# MegaShieldDB.net
KiCad netlist of a schematic drawn in EAGLE
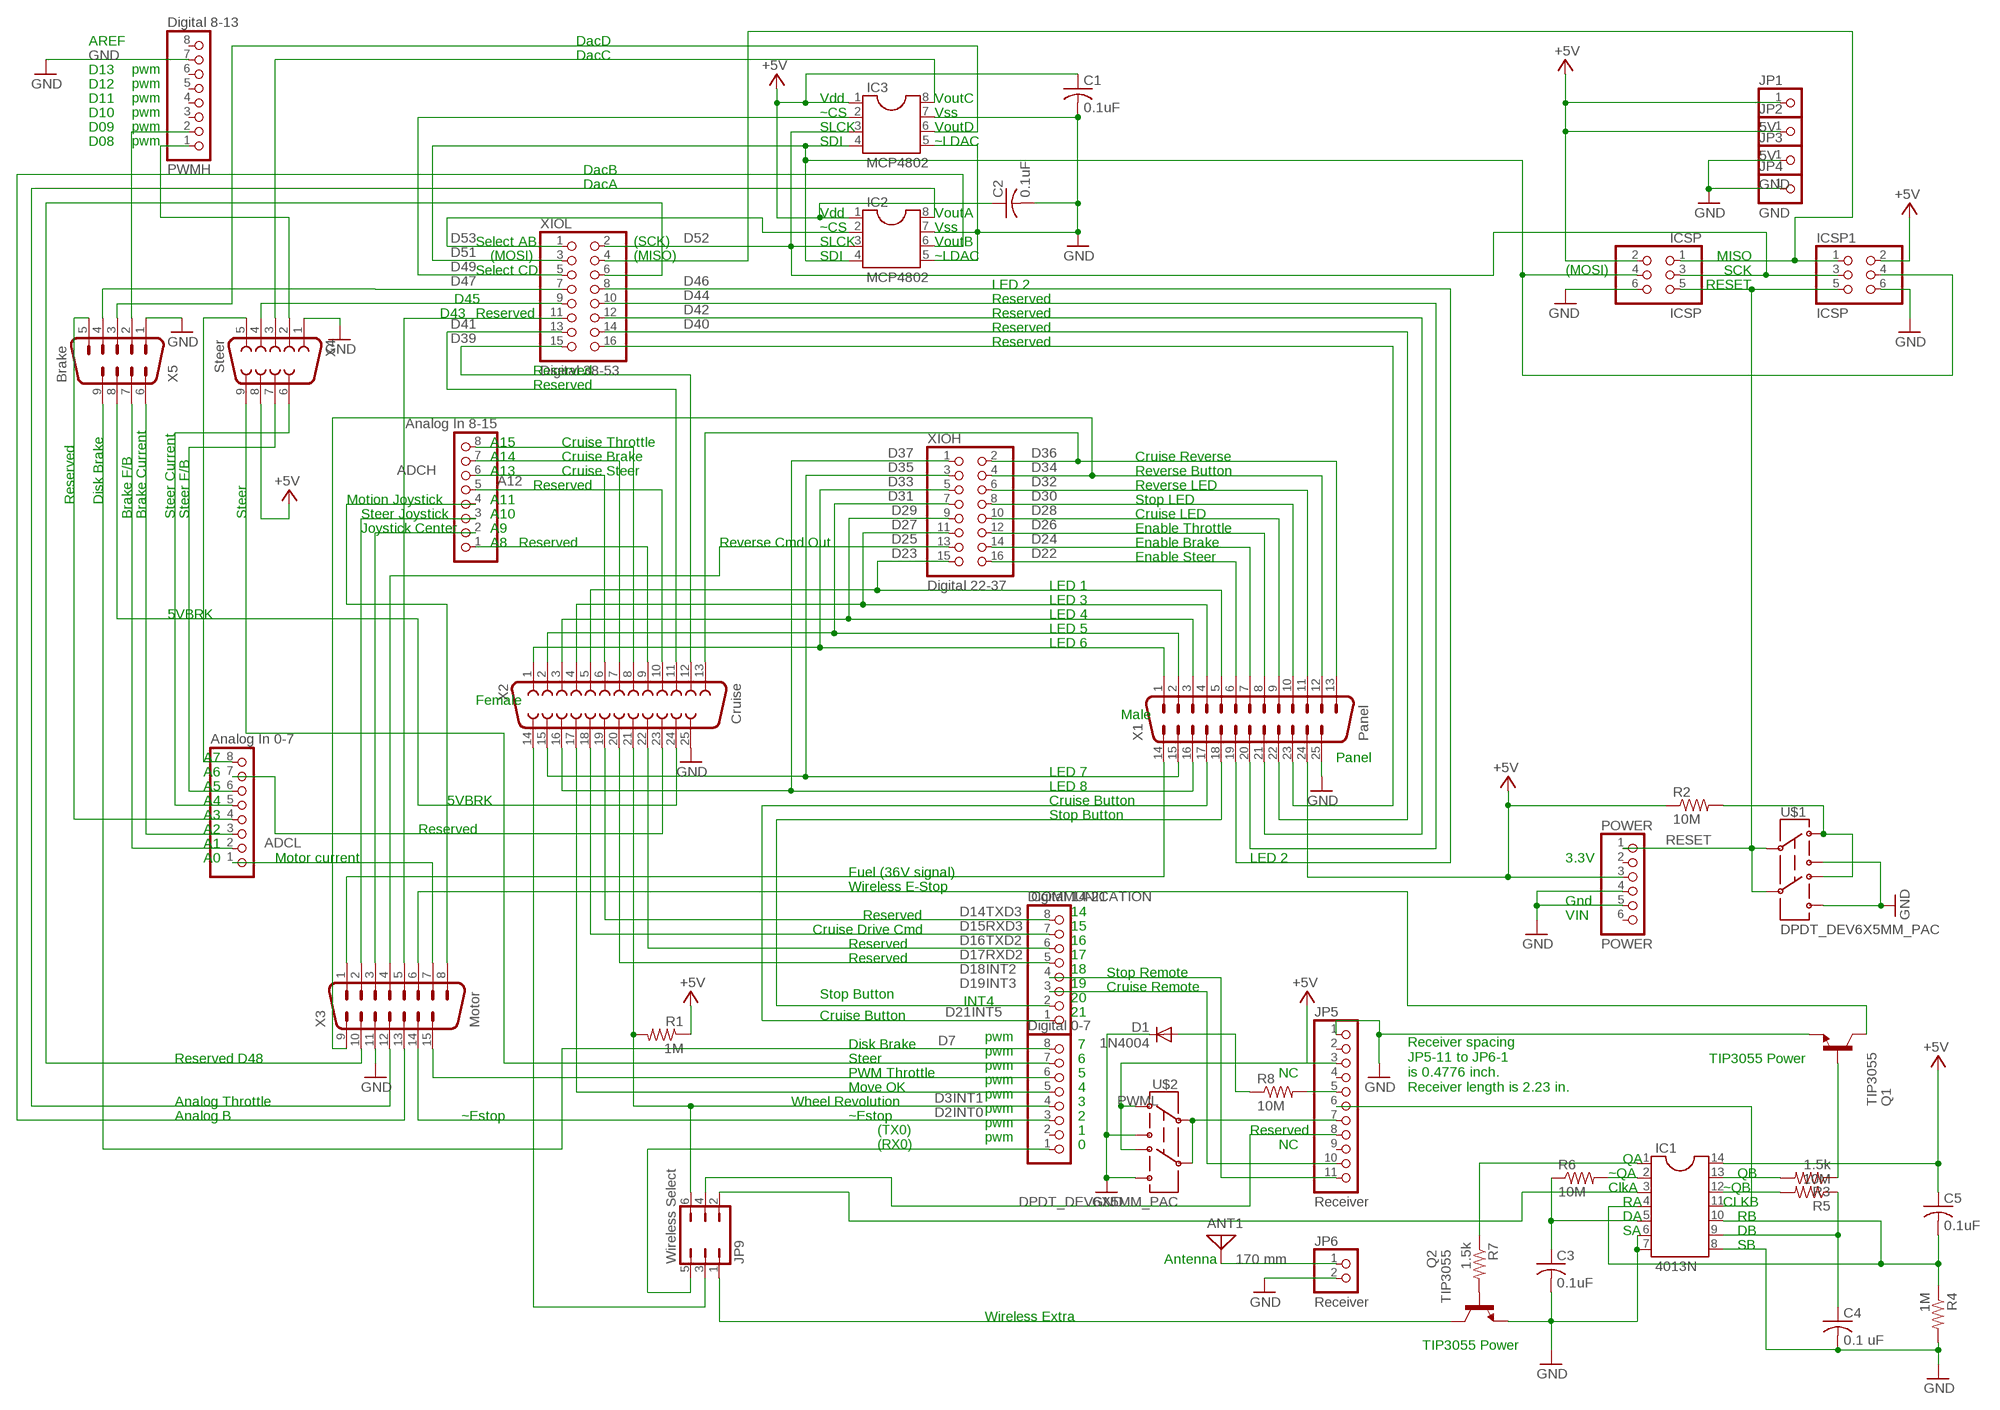
[diagram p0: schematic, sheet 1]

(export (version "E")
  (design (tool "Eeschema 10.0.6"))
  (components
    (comp (ref "ADCH")
      (value "Analog In 8-15")
      (footprint "eagle-import:1X08")
      (libsource (lib "eagle-import") (part "PINHD-1X8"))
    )
    (comp (ref "ADCL")
      (value "Analog In 0-7")
      (footprint "eagle-import:1X08")
      (libsource (lib "eagle-import") (part "PINHD-1X8"))
    )
    (comp (ref "ANT1")
      (value "170 mm")
      (footprint "eagle-import:PAD-01")
      (libsource (lib "eagle-import") (part "ANTENNA"))
    )
    (comp (ref "C1")
      (value "0.1uF")
      (footprint "eagle-import:C025-025X050")
      (libsource (lib "eagle-import") (part "C-US025-025X050"))
    )
    (comp (ref "C2")
      (value "0.1uF")
      (footprint "eagle-import:C025-025X050")
      (libsource (lib "eagle-import") (part "C-US025-025X050"))
    )
    (comp (ref "C3")
      (value "0.1uF")
      (footprint "eagle-import:C025-025X050")
      (libsource (lib "eagle-import") (part "C-US025-025X050"))
    )
    (comp (ref "C4")
      (value "0.1 uF")
      (footprint "eagle-import:C025-025X050")
      (libsource (lib "eagle-import") (part "C-US025-025X050"))
    )
    (comp (ref "C5")
      (value "0.1uF")
      (footprint "eagle-import:C025-025X050")
      (libsource (lib "eagle-import") (part "C-US025-025X050"))
    )
    (comp (ref "COMMUNICATION")
      (value "Digital 14-21")
      (footprint "eagle-import:1X08")
      (libsource (lib "eagle-import") (part "PINHD-1X8"))
    )
    (comp (ref "D1")
      (value "1N4004")
      (footprint "eagle-import:DO41-10")
      (libsource (lib "eagle-import") (part "1N4004"))
    )
    (comp (ref "IC1")
      (value "4013N")
      (footprint "eagle-import:DIL14")
      (libsource (lib "eagle-import") (part "DIL14"))
    )
    (comp (ref "IC2")
      (value "MCP4802")
      (footprint "eagle-import:DIL08")
      (libsource (lib "eagle-import") (part "DIL8"))
    )
    (comp (ref "IC3")
      (value "MCP4802")
      (footprint "eagle-import:DIL08")
      (libsource (lib "eagle-import") (part "DIL8"))
    )
    (comp (ref "ICSP")
      (value "ICSP")
      (footprint "eagle-import:2X03")
      (libsource (lib "eagle-import") (part "PINHD-2X3"))
    )
    (comp (ref "ICSP1")
      (value "ICSP")
      (footprint "eagle-import:2X03")
      (libsource (lib "eagle-import") (part "PINHD-2X3"))
    )
    (comp (ref "JP1")
      (value "5V")
      (footprint "eagle-import:1X01")
      (libsource (lib "eagle-import") (part "PINHD-1X1"))
    )
    (comp (ref "JP2")
      (value "5V")
      (footprint "eagle-import:1X01")
      (libsource (lib "eagle-import") (part "PINHD-1X1"))
    )
    (comp (ref "JP3")
      (value "GND")
      (footprint "eagle-import:1X01")
      (libsource (lib "eagle-import") (part "PINHD-1X1"))
    )
    (comp (ref "JP4")
      (value "GND")
      (footprint "eagle-import:1X01")
      (libsource (lib "eagle-import") (part "PINHD-1X1"))
    )
    (comp (ref "JP5")
      (value "Receiver")
      (footprint "eagle-import:1X11")
      (libsource (lib "eagle-import") (part "PINHD-1X11"))
    )
    (comp (ref "JP6")
      (value "Receiver")
      (footprint "eagle-import:1X02")
      (libsource (lib "eagle-import") (part "PINHD-1X2"))
    )
    (comp (ref "JP9")
      (value "Wireless Select")
      (footprint "eagle-import:JP3Q")
      (libsource (lib "eagle-import") (part "JP3Q"))
    )
    (comp (ref "POWER")
      (value "POWER")
      (footprint "eagle-import:1X06")
      (libsource (lib "eagle-import") (part "PINHD-1X6"))
    )
    (comp (ref "PWMH")
      (value "Digital 8-13")
      (footprint "eagle-import:1X08")
      (libsource (lib "eagle-import") (part "PINHD-1X8"))
    )
    (comp (ref "PWML")
      (value "Digital 0-7")
      (footprint "eagle-import:1X08")
      (libsource (lib "eagle-import") (part "PINHD-1X8"))
    )
    (comp (ref "Q1")
      (value "TIP3055")
      (footprint "eagle-import:TO220")
      (libsource (lib "eagle-import") (part "BD535"))
    )
    (comp (ref "Q2")
      (value "TIP3055")
      (footprint "eagle-import:TO220")
      (libsource (lib "eagle-import") (part "BD535"))
    )
    (comp (ref "R1")
      (value "1M")
      (footprint "eagle-import:0204_5")
      (libsource (lib "eagle-import") (part "R-US_0204/5"))
    )
    (comp (ref "R2")
      (value "10M")
      (footprint "eagle-import:0204_5")
      (libsource (lib "eagle-import") (part "R-US_0204/5"))
    )
    (comp (ref "R3")
      (value "1.5k")
      (footprint "eagle-import:0204_5")
      (libsource (lib "eagle-import") (part "R-US_0204/5"))
    )
    (comp (ref "R4")
      (value "1M")
      (footprint "eagle-import:0204_5")
      (libsource (lib "eagle-import") (part "R-US_0204/5"))
    )
    (comp (ref "R5")
      (value "10M")
      (footprint "eagle-import:0204_5")
      (libsource (lib "eagle-import") (part "R-US_0204/5"))
    )
    (comp (ref "R6")
      (value "10M")
      (footprint "eagle-import:0204_5")
      (libsource (lib "eagle-import") (part "R-US_0204/5"))
    )
    (comp (ref "R7")
      (value "1.5k")
      (footprint "eagle-import:0204_5")
      (libsource (lib "eagle-import") (part "R-US_0204/5"))
    )
    (comp (ref "R8")
      (value "10M")
      (footprint "eagle-import:0204_5")
      (libsource (lib "eagle-import") (part "R-US_0204/5"))
    )
    (comp (ref "U$1")
      (value "DPDT_DEV6X5MM_PAC")
      (footprint "eagle-import:NEWSWITCH2_PAC")
      (libsource (lib "eagle-import") (part "DPDT_DEV6X5MM_PAC"))
    )
    (comp (ref "U$2")
      (value "DPDT_DEV6X5MM_PAC")
      (footprint "eagle-import:NEWSWITCH2_PAC")
      (libsource (lib "eagle-import") (part "DPDT_DEV6X5MM_PAC"))
    )
    (comp (ref "X1")
      (value "Panel")
      (footprint "eagle-import:M25-HD-20")
      (libsource (lib "eagle-import") (part "M25-HD-20"))
    )
    (comp (ref "X2")
      (value "Cruise")
      (footprint "eagle-import:F25H")
      (libsource (lib "eagle-import") (part "F25H"))
    )
    (comp (ref "X3")
      (value "Motor")
      (footprint "eagle-import:182-015-MALE")
      (libsource (lib "eagle-import") (part "M15-182"))
    )
    (comp (ref "X4")
      (value "Steer")
      (footprint "eagle-import:F09H")
      (libsource (lib "eagle-import") (part "F09H"))
    )
    (comp (ref "X5")
      (value "Brake")
      (footprint "eagle-import:182-009-MALE")
      (libsource (lib "eagle-import") (part "M09-182"))
    )
    (comp (ref "XIOH")
      (value "Digital 22-37")
      (footprint "eagle-import:2X08")
      (libsource (lib "eagle-import") (part "PINHD-2X8"))
    )
    (comp (ref "XIOL")
      (value "Digital 38-53")
      (footprint "eagle-import:2X08")
      (libsource (lib "eagle-import") (part "PINHD-2X8"))
    )
  )
  (nets
    (net (code "1") (name "+5V") (class "Default")
      (node (ref "C1") (pin "1") (pinfunction "1_1") (pintype "passive"))
      (node (ref "C2") (pin "1") (pinfunction "1_1") (pintype "passive"))
      (node (ref "C5") (pin "1") (pinfunction "1_1") (pintype "passive"))
      (node (ref "IC1") (pin "14") (pinfunction "14_14") (pintype "passive"))
      (node (ref "IC2") (pin "1") (pinfunction "1_1") (pintype "passive"))
      (node (ref "IC3") (pin "1") (pinfunction "1_1") (pintype "passive"))
      (node (ref "ICSP") (pin "2") (pinfunction "2_2") (pintype "passive"))
      (node (ref "ICSP1") (pin "2") (pinfunction "2_2") (pintype "passive"))
      (node (ref "JP1") (pin "1") (pinfunction "1_1") (pintype "passive"))
      (node (ref "JP2") (pin "1") (pinfunction "1_1") (pintype "passive"))
      (node (ref "JP5") (pin "3") (pinfunction "3_3") (pintype "passive"))
      (node (ref "POWER") (pin "3") (pinfunction "3_3") (pintype "passive"))
      (node (ref "R1") (pin "1") (pinfunction "1_1") (pintype "passive"))
      (node (ref "R2") (pin "1") (pinfunction "1_1") (pintype "passive"))
      (node (ref "U$2") (pin "PIN1") (pinfunction "1_PIN1") (pintype "bidirectional"))
      (node (ref "U$2") (pin "PIN4") (pinfunction "4_PIN4") (pintype "bidirectional"))
      (node (ref "X1") (pin "24") (pinfunction "24_24") (pintype "passive"))
      (node (ref "X4") (pin "8") (pinfunction "8_8") (pintype "passive"))
    )
    (net (code "2") (name "/A12") (class "Default")
      (node (ref "ADCH") (pin "5") (pinfunction "5_5") (pintype "passive"))
      (node (ref "X2") (pin "10") (pinfunction "10_10") (pintype "passive"))
    )
    (net (code "3") (name "/D2INT0") (class "Default")
      (node (ref "PWML") (pin "3") (pinfunction "3_3") (pintype "passive"))
      (node (ref "X3") (pin "14") (pinfunction "14_14") (pintype "passive"))
    )
    (net (code "4") (name "/D3INT1") (class "Default")
      (node (ref "JP9") (pin "6") (pinfunction "6_6") (pintype "passive"))
      (node (ref "PWML") (pin "4") (pinfunction "4_4") (pintype "passive"))
      (node (ref "R1") (pin "2") (pinfunction "2_2") (pintype "passive"))
      (node (ref "X2") (pin "21") (pinfunction "21_21") (pintype "passive"))
    )
    (net (code "5") (name "/D7") (class "Default")
      (node (ref "PWML") (pin "8") (pinfunction "8_8") (pintype "passive"))
      (node (ref "X5") (pin "9") (pinfunction "9_9") (pintype "passive"))
    )
    (net (code "6") (name "/D14TXD3") (class "Default")
      (node (ref "COMMUNICATION") (pin "8") (pinfunction "8_8") (pintype "passive"))
      (node (ref "X2") (pin "19") (pinfunction "19_19") (pintype "passive"))
    )
    (net (code "7") (name "/D15RXD3") (class "Default")
      (node (ref "COMMUNICATION") (pin "7") (pinfunction "7_7") (pintype "passive"))
      (node (ref "X2") (pin "18") (pinfunction "18_18") (pintype "passive"))
    )
    (net (code "8") (name "/D16TXD2") (class "Default")
      (node (ref "COMMUNICATION") (pin "6") (pinfunction "6_6") (pintype "passive"))
      (node (ref "X2") (pin "22") (pinfunction "22_22") (pintype "passive"))
    )
    (net (code "9") (name "/D17RXD2") (class "Default")
      (node (ref "COMMUNICATION") (pin "5") (pinfunction "5_5") (pintype "passive"))
      (node (ref "X2") (pin "20") (pinfunction "20_20") (pintype "passive"))
    )
    (net (code "10") (name "/D18INT2") (class "Default")
      (node (ref "COMMUNICATION") (pin "4") (pinfunction "4_4") (pintype "passive"))
      (node (ref "JP5") (pin "11") (pinfunction "11_11") (pintype "passive"))
    )
    (net (code "11") (name "/D19INT3") (class "Default")
      (node (ref "COMMUNICATION") (pin "3") (pinfunction "3_3") (pintype "passive"))
      (node (ref "JP5") (pin "10") (pinfunction "10_10") (pintype "passive"))
    )
    (net (code "12") (name "/D21INT5") (class "Default")
      (node (ref "COMMUNICATION") (pin "1") (pinfunction "1_1") (pintype "passive"))
      (node (ref "X1") (pin "17") (pinfunction "17_17") (pintype "passive"))
    )
    (net (code "13") (name "/D22") (class "Default")
      (node (ref "X1") (pin "6") (pinfunction "6_6") (pintype "passive"))
      (node (ref "XIOH") (pin "16") (pinfunction "16_16") (pintype "passive"))
    )
    (net (code "14") (name "/D23") (class "Default")
      (node (ref "X1") (pin "5") (pinfunction "5_5") (pintype "passive"))
      (node (ref "X2") (pin "5") (pinfunction "5_5") (pintype "passive"))
      (node (ref "XIOH") (pin "15") (pinfunction "15_15") (pintype "passive"))
    )
    (net (code "15") (name "/D24") (class "Default")
      (node (ref "X1") (pin "7") (pinfunction "7_7") (pintype "passive"))
      (node (ref "XIOH") (pin "14") (pinfunction "14_14") (pintype "passive"))
    )
    (net (code "16") (name "/D25") (class "Default")
      (node (ref "X3") (pin "4") (pinfunction "4_4") (pintype "passive"))
      (node (ref "XIOH") (pin "13") (pinfunction "13_13") (pintype "passive"))
    )
    (net (code "17") (name "/D26") (class "Default")
      (node (ref "X1") (pin "8") (pinfunction "8_8") (pintype "passive"))
      (node (ref "XIOH") (pin "12") (pinfunction "12_12") (pintype "passive"))
    )
    (net (code "18") (name "/D27") (class "Default")
      (node (ref "X1") (pin "4") (pinfunction "4_4") (pintype "passive"))
      (node (ref "X2") (pin "4") (pinfunction "4_4") (pintype "passive"))
      (node (ref "XIOH") (pin "11") (pinfunction "11_11") (pintype "passive"))
    )
    (net (code "19") (name "/D28") (class "Default")
      (node (ref "X1") (pin "9") (pinfunction "9_9") (pintype "passive"))
      (node (ref "XIOH") (pin "10") (pinfunction "10_10") (pintype "passive"))
    )
    (net (code "20") (name "/D29") (class "Default")
      (node (ref "X1") (pin "3") (pinfunction "3_3") (pintype "passive"))
      (node (ref "X2") (pin "3") (pinfunction "3_3") (pintype "passive"))
      (node (ref "XIOH") (pin "9") (pinfunction "9_9") (pintype "passive"))
    )
    (net (code "21") (name "/D30") (class "Default")
      (node (ref "X1") (pin "10") (pinfunction "10_10") (pintype "passive"))
      (node (ref "XIOH") (pin "8") (pinfunction "8_8") (pintype "passive"))
    )
    (net (code "22") (name "/D31") (class "Default")
      (node (ref "X1") (pin "2") (pinfunction "2_2") (pintype "passive"))
      (node (ref "X2") (pin "2") (pinfunction "2_2") (pintype "passive"))
      (node (ref "XIOH") (pin "7") (pinfunction "7_7") (pintype "passive"))
    )
    (net (code "23") (name "/D32") (class "Default")
      (node (ref "X1") (pin "11") (pinfunction "11_11") (pintype "passive"))
      (node (ref "XIOH") (pin "6") (pinfunction "6_6") (pintype "passive"))
    )
    (net (code "24") (name "/D33") (class "Default")
      (node (ref "X1") (pin "1") (pinfunction "1_1") (pintype "passive"))
      (node (ref "X2") (pin "1") (pinfunction "1_1") (pintype "passive"))
      (node (ref "XIOH") (pin "5") (pinfunction "5_5") (pintype "passive"))
    )
    (net (code "25") (name "/D34") (class "Default")
      (node (ref "X1") (pin "12") (pinfunction "12_12") (pintype "passive"))
      (node (ref "X3") (pin "9") (pinfunction "9_9") (pintype "passive"))
      (node (ref "XIOH") (pin "4") (pinfunction "4_4") (pintype "passive"))
    )
    (net (code "26") (name "/D35") (class "Default")
      (node (ref "X1") (pin "15") (pinfunction "15_15") (pintype "passive"))
      (node (ref "X2") (pin "15") (pinfunction "15_15") (pintype "passive"))
      (node (ref "XIOH") (pin "3") (pinfunction "3_3") (pintype "passive"))
    )
    (net (code "27") (name "/D36") (class "Default")
      (node (ref "X1") (pin "13") (pinfunction "13_13") (pintype "passive"))
      (node (ref "X2") (pin "13") (pinfunction "13_13") (pintype "passive"))
      (node (ref "XIOH") (pin "2") (pinfunction "2_2") (pintype "passive"))
    )
    (net (code "28") (name "/D37") (class "Default")
      (node (ref "X1") (pin "16") (pinfunction "16_16") (pintype "passive"))
      (node (ref "X2") (pin "16") (pinfunction "16_16") (pintype "passive"))
      (node (ref "XIOH") (pin "1") (pinfunction "1_1") (pintype "passive"))
    )
    (net (code "29") (name "/D39") (class "Default")
      (node (ref "X2") (pin "12") (pinfunction "12_12") (pintype "passive"))
      (node (ref "XIOL") (pin "15") (pinfunction "15_15") (pintype "passive"))
    )
    (net (code "30") (name "/D40") (class "Default")
      (node (ref "X1") (pin "22") (pinfunction "22_22") (pintype "passive"))
      (node (ref "XIOL") (pin "14") (pinfunction "14_14") (pintype "passive"))
    )
    (net (code "31") (name "/D41") (class "Default")
      (node (ref "X2") (pin "11") (pinfunction "11_11") (pintype "passive"))
      (node (ref "XIOL") (pin "13") (pinfunction "13_13") (pintype "passive"))
    )
    (net (code "32") (name "/D42") (class "Default")
      (node (ref "X1") (pin "21") (pinfunction "21_21") (pintype "passive"))
      (node (ref "XIOL") (pin "12") (pinfunction "12_12") (pintype "passive"))
    )
    (net (code "33") (name "/D44") (class "Default")
      (node (ref "X1") (pin "20") (pinfunction "20_20") (pintype "passive"))
      (node (ref "XIOL") (pin "10") (pinfunction "10_10") (pintype "passive"))
    )
    (net (code "34") (name "/D46") (class "Default")
      (node (ref "X1") (pin "19") (pinfunction "19_19") (pintype "passive"))
      (node (ref "XIOL") (pin "8") (pinfunction "8_8") (pintype "passive"))
    )
    (net (code "35") (name "/D47") (class "Default")
      (node (ref "X5") (pin "4") (pinfunction "4_4") (pintype "passive"))
      (node (ref "XIOL") (pin "7") (pinfunction "7_7") (pintype "passive"))
    )
    (net (code "36") (name "/D49") (class "Default")
      (node (ref "IC3") (pin "2") (pinfunction "2_2") (pintype "passive"))
      (node (ref "XIOL") (pin "5") (pinfunction "5_5") (pintype "passive"))
    )
    (net (code "37") (name "/D51") (class "Default")
      (node (ref "IC2") (pin "4") (pinfunction "4_4") (pintype "passive"))
      (node (ref "IC3") (pin "4") (pinfunction "4_4") (pintype "passive"))
      (node (ref "ICSP") (pin "4") (pinfunction "4_4") (pintype "passive"))
      (node (ref "ICSP1") (pin "4") (pinfunction "4_4") (pintype "passive"))
      (node (ref "XIOL") (pin "3") (pinfunction "3_3") (pintype "passive"))
    )
    (net (code "38") (name "/D52") (class "Default")
      (node (ref "IC2") (pin "3") (pinfunction "3_3") (pintype "passive"))
      (node (ref "IC3") (pin "3") (pinfunction "3_3") (pintype "passive"))
      (node (ref "ICSP") (pin "3") (pinfunction "3_3") (pintype "passive"))
      (node (ref "ICSP1") (pin "3") (pinfunction "3_3") (pintype "passive"))
      (node (ref "XIOL") (pin "2") (pinfunction "2_2") (pintype "passive"))
    )
    (net (code "39") (name "/D53") (class "Default")
      (node (ref "IC2") (pin "2") (pinfunction "2_2") (pintype "passive"))
      (node (ref "XIOL") (pin "1") (pinfunction "1_1") (pintype "passive"))
    )
    (net (code "40") (name "/RESET") (class "Default")
      (node (ref "ICSP") (pin "5") (pinfunction "5_5") (pintype "passive"))
      (node (ref "ICSP1") (pin "5") (pinfunction "5_5") (pintype "passive"))
      (node (ref "POWER") (pin "1") (pinfunction "1_1") (pintype "passive"))
      (node (ref "U$1") (pin "PIN2") (pinfunction "2_PIN2") (pintype "bidirectional"))
      (node (ref "U$1") (pin "PIN5") (pinfunction "5_PIN5") (pintype "bidirectional"))
    )
    (net (code "41") (name "GND") (class "Default")
      (node (ref "C1") (pin "2") (pinfunction "2_2") (pintype "passive"))
      (node (ref "C2") (pin "2") (pinfunction "2_2") (pintype "passive"))
      (node (ref "C3") (pin "2") (pinfunction "2_2") (pintype "passive"))
      (node (ref "C4") (pin "2") (pinfunction "2_2") (pintype "passive"))
      (node (ref "D1") (pin "C") (pinfunction "C_C") (pintype "passive"))
      (node (ref "IC1") (pin "6") (pinfunction "6_6") (pintype "passive"))
      (node (ref "IC1") (pin "7") (pinfunction "7_7") (pintype "passive"))
      (node (ref "IC1") (pin "8") (pinfunction "8_8") (pintype "passive"))
      (node (ref "IC2") (pin "5") (pinfunction "5_5") (pintype "passive"))
      (node (ref "IC2") (pin "7") (pinfunction "7_7") (pintype "passive"))
      (node (ref "IC3") (pin "5") (pinfunction "5_5") (pintype "passive"))
      (node (ref "IC3") (pin "7") (pinfunction "7_7") (pintype "passive"))
      (node (ref "ICSP") (pin "6") (pinfunction "6_6") (pintype "passive"))
      (node (ref "ICSP1") (pin "6") (pinfunction "6_6") (pintype "passive"))
      (node (ref "JP3") (pin "1") (pinfunction "1_1") (pintype "passive"))
      (node (ref "JP4") (pin "1") (pinfunction "1_1") (pintype "passive"))
      (node (ref "JP5") (pin "1") (pinfunction "1_1") (pintype "passive"))
      (node (ref "JP6") (pin "2") (pinfunction "2_2") (pintype "passive"))
      (node (ref "POWER") (pin "4") (pinfunction "4_4") (pintype "passive"))
      (node (ref "POWER") (pin "5") (pinfunction "5_5") (pintype "passive"))
      (node (ref "PWMH") (pin "7") (pinfunction "7_7") (pintype "passive"))
      (node (ref "Q1") (pin "1") (pinfunction "E_1") (pintype "passive"))
      (node (ref "Q2") (pin "1") (pinfunction "E_1") (pintype "passive"))
      (node (ref "R4") (pin "2") (pinfunction "2_2") (pintype "passive"))
      (node (ref "U$1") (pin "PIN3") (pinfunction "3_PIN3") (pintype "bidirectional"))
      (node (ref "U$1") (pin "PIN6") (pinfunction "6_PIN6") (pintype "bidirectional"))
      (node (ref "U$2") (pin "PIN3") (pinfunction "3_PIN3") (pintype "bidirectional"))
      (node (ref "U$2") (pin "PIN6") (pinfunction "6_PIN6") (pintype "bidirectional"))
      (node (ref "X1") (pin "25") (pinfunction "25_25") (pintype "passive"))
      (node (ref "X2") (pin "25") (pinfunction "25_25") (pintype "passive"))
      (node (ref "X3") (pin "11") (pinfunction "11_11") (pintype "passive"))
      (node (ref "X4") (pin "1") (pinfunction "1_1") (pintype "passive"))
      (node (ref "X5") (pin "1") (pinfunction "1_1") (pintype "passive"))
    )
    (net (code "42") (name "Net-(ADCH-Pad1)") (class "Default")
      (node (ref "ADCH") (pin "1") (pinfunction "1_1") (pintype "passive"))
      (node (ref "X2") (pin "9") (pinfunction "9_9") (pintype "passive"))
    )
    (net (code "43") (name "Net-(ADCH-Pad2)") (class "Default")
      (node (ref "ADCH") (pin "2") (pinfunction "2_2") (pintype "passive"))
      (node (ref "X3") (pin "3") (pinfunction "3_3") (pintype "passive"))
    )
    (net (code "44") (name "Net-(ADCH-Pad3)") (class "Default")
      (node (ref "ADCH") (pin "3") (pinfunction "3_3") (pintype "passive"))
      (node (ref "X3") (pin "2") (pinfunction "2_2") (pintype "passive"))
    )
    (net (code "45") (name "Net-(ADCH-Pad4)") (class "Default")
      (node (ref "ADCH") (pin "4") (pinfunction "4_4") (pintype "passive"))
      (node (ref "X3") (pin "8") (pinfunction "8_8") (pintype "passive"))
    )
    (net (code "46") (name "Net-(ADCH-Pad6)") (class "Default")
      (node (ref "ADCH") (pin "6") (pinfunction "6_6") (pintype "passive"))
      (node (ref "X2") (pin "6") (pinfunction "6_6") (pintype "passive"))
    )
    (net (code "47") (name "Net-(ADCH-Pad7)") (class "Default")
      (node (ref "ADCH") (pin "7") (pinfunction "7_7") (pintype "passive"))
      (node (ref "X2") (pin "7") (pinfunction "7_7") (pintype "passive"))
    )
    (net (code "48") (name "Net-(ADCH-Pad8)") (class "Default")
      (node (ref "ADCH") (pin "8") (pinfunction "8_8") (pintype "passive"))
      (node (ref "X2") (pin "8") (pinfunction "8_8") (pintype "passive"))
    )
    (net (code "49") (name "Net-(ADCL-Pad1)") (class "Default")
      (node (ref "ADCL") (pin "1") (pinfunction "1_1") (pintype "passive"))
      (node (ref "X3") (pin "7") (pinfunction "7_7") (pintype "passive"))
    )
    (net (code "50") (name "Net-(ADCL-Pad2)") (class "Default")
      (node (ref "ADCL") (pin "2") (pinfunction "2_2") (pintype "passive"))
      (node (ref "X5") (pin "7") (pinfunction "7_7") (pintype "passive"))
    )
    (net (code "51") (name "Net-(ADCL-Pad3)") (class "Default")
      (node (ref "ADCL") (pin "3") (pinfunction "3_3") (pintype "passive"))
      (node (ref "X5") (pin "6") (pinfunction "6_6") (pintype "passive"))
    )
    (net (code "52") (name "Net-(ADCL-Pad4)") (class "Default")
      (node (ref "ADCL") (pin "4") (pinfunction "4_4") (pintype "passive"))
      (node (ref "X5") (pin "5") (pinfunction "5_5") (pintype "passive"))
    )
    (net (code "53") (name "Net-(ADCL-Pad5)") (class "Default")
      (node (ref "ADCL") (pin "5") (pinfunction "5_5") (pintype "passive"))
      (node (ref "X4") (pin "6") (pinfunction "6_6") (pintype "passive"))
    )
    (net (code "54") (name "Net-(ADCL-Pad6)") (class "Default")
      (node (ref "ADCL") (pin "6") (pinfunction "6_6") (pintype "passive"))
      (node (ref "X4") (pin "7") (pinfunction "7_7") (pintype "passive"))
    )
    (net (code "55") (name "Net-(ADCL-Pad7)") (class "Default")
      (node (ref "ADCL") (pin "7") (pinfunction "7_7") (pintype "passive"))
      (node (ref "X2") (pin "23") (pinfunction "23_23") (pintype "passive"))
    )
    (net (code "56") (name "Net-(ADCL-Pad8)") (class "Default")
      (node (ref "ADCL") (pin "8") (pinfunction "8_8") (pintype "passive"))
      (node (ref "X4") (pin "5") (pinfunction "5_5") (pintype "passive"))
    )
    (net (code "57") (name "Net-(ANT1-Pad1)") (class "Default")
      (node (ref "ANT1") (pin "1") (pinfunction "1_1") (pintype "output"))
      (node (ref "JP6") (pin "1") (pinfunction "1_1") (pintype "passive"))
    )
    (net (code "58") (name "Net-(C3-Pad1)") (class "Default")
      (node (ref "C3") (pin "1") (pinfunction "1_1") (pintype "passive"))
      (node (ref "IC1") (pin "5") (pinfunction "5_5") (pintype "passive"))
      (node (ref "R6") (pin "1") (pinfunction "1_1") (pintype "passive"))
    )
    (net (code "59") (name "Net-(C4-Pad1)") (class "Default")
      (node (ref "C4") (pin "1") (pinfunction "1_1") (pintype "passive"))
      (node (ref "IC1") (pin "9") (pinfunction "9_9") (pintype "passive"))
      (node (ref "R5") (pin "1") (pinfunction "1_1") (pintype "passive"))
    )
    (net (code "60") (name "Net-(C5-Pad2)") (class "Default")
      (node (ref "C5") (pin "2") (pinfunction "2_2") (pintype "passive"))
      (node (ref "IC1") (pin "10") (pinfunction "10_10") (pintype "passive"))
      (node (ref "IC1") (pin "4") (pinfunction "4_4") (pintype "passive"))
      (node (ref "R4") (pin "1") (pinfunction "1_1") (pintype "passive"))
    )
    (net (code "61") (name "Net-(COMMUNICATION-Pad2)") (class "Default")
      (node (ref "COMMUNICATION") (pin "2") (pinfunction "2_2") (pintype "passive"))
      (node (ref "X1") (pin "18") (pinfunction "18_18") (pintype "passive"))
    )
    (net (code "62") (name "Net-(D1-PadA)") (class "Default")
      (node (ref "D1") (pin "A") (pinfunction "A_A") (pintype "passive"))
      (node (ref "R8") (pin "1") (pinfunction "1_1") (pintype "passive"))
    )
    (net (code "63") (name "Net-(IC1-Pad1)") (class "Default")
      (node (ref "IC1") (pin "1") (pinfunction "1_1") (pintype "passive"))
      (node (ref "R7") (pin "1") (pinfunction "1_1") (pintype "passive"))
    )
    (net (code "64") (name "Net-(IC1-Pad2)") (class "Default")
      (node (ref "IC1") (pin "2") (pinfunction "2_2") (pintype "passive"))
      (node (ref "R6") (pin "2") (pinfunction "2_2") (pintype "passive"))
    )
    (net (code "65") (name "Net-(IC1-Pad3)") (class "Default")
      (node (ref "IC1") (pin "3") (pinfunction "3_3") (pintype "passive"))
      (node (ref "JP9") (pin "2") (pinfunction "2_2") (pintype "passive"))
    )
    (net (code "66") (name "Net-(IC1-Pad11)") (class "Default")
      (node (ref "IC1") (pin "11") (pinfunction "11_11") (pintype "passive"))
      (node (ref "JP5") (pin "6") (pinfunction "6_6") (pintype "passive"))
    )
    (net (code "67") (name "Net-(IC1-Pad12)") (class "Default")
      (node (ref "IC1") (pin "12") (pinfunction "12_12") (pintype "passive"))
      (node (ref "R5") (pin "2") (pinfunction "2_2") (pintype "passive"))
    )
    (net (code "68") (name "Net-(IC1-Pad13)") (class "Default")
      (node (ref "IC1") (pin "13") (pinfunction "13_13") (pintype "passive"))
      (node (ref "R3") (pin "2") (pinfunction "2_2") (pintype "passive"))
    )
    (net (code "69") (name "Net-(IC2-Pad6)") (class "Default")
      (node (ref "IC2") (pin "6") (pinfunction "6_6") (pintype "passive"))
      (node (ref "X3") (pin "13") (pinfunction "13_13") (pintype "passive"))
    )
    (net (code "70") (name "Net-(IC2-Pad8)") (class "Default")
      (node (ref "IC2") (pin "8") (pinfunction "8_8") (pintype "passive"))
      (node (ref "X3") (pin "12") (pinfunction "12_12") (pintype "passive"))
    )
    (net (code "71") (name "Net-(IC3-Pad6)") (class "Default")
      (node (ref "IC3") (pin "6") (pinfunction "6_6") (pintype "passive"))
      (node (ref "X5") (pin "3") (pinfunction "3_3") (pintype "passive"))
    )
    (net (code "72") (name "Net-(IC3-Pad8)") (class "Default")
      (node (ref "IC3") (pin "8") (pinfunction "8_8") (pintype "passive"))
      (node (ref "X4") (pin "3") (pinfunction "3_3") (pintype "passive"))
    )
    (net (code "73") (name "Net-(ICSP-Pad1)") (class "Default")
      (node (ref "ICSP") (pin "1") (pinfunction "1_1") (pintype "passive"))
      (node (ref "ICSP1") (pin "1") (pinfunction "1_1") (pintype "passive"))
      (node (ref "XIOL") (pin "4") (pinfunction "4_4") (pintype "passive"))
    )
    (net (code "74") (name "Net-(JP5-Pad5)") (class "Default")
      (node (ref "JP5") (pin "5") (pinfunction "5_5") (pintype "passive"))
      (node (ref "R8") (pin "2") (pinfunction "2_2") (pintype "passive"))
    )
    (net (code "75") (name "Net-(JP5-Pad8)") (class "Default")
      (node (ref "JP5") (pin "8") (pinfunction "8_8") (pintype "passive"))
      (node (ref "JP9") (pin "4") (pinfunction "4_4") (pintype "passive"))
    )
    (net (code "76") (name "Net-(JP9-Pad3)") (class "Default")
      (node (ref "JP9") (pin "3") (pinfunction "3_3") (pintype "passive"))
      (node (ref "X2") (pin "14") (pinfunction "14_14") (pintype "passive"))
    )
    (net (code "77") (name "Net-(JP9-Pad5)") (class "Default")
      (node (ref "JP9") (pin "5") (pinfunction "5_5") (pintype "passive"))
      (node (ref "PWML") (pin "1") (pinfunction "1_1") (pintype "passive"))
    )
    (net (code "78") (name "Net-(PWMH-Pad1)") (class "Default")
      (node (ref "PWMH") (pin "1") (pinfunction "1_1") (pintype "passive"))
      (node (ref "X4") (pin "2") (pinfunction "2_2") (pintype "passive"))
    )
    (net (code "79") (name "Net-(PWMH-Pad2)") (class "Default")
      (node (ref "PWMH") (pin "2") (pinfunction "2_2") (pintype "passive"))
      (node (ref "X5") (pin "2") (pinfunction "2_2") (pintype "passive"))
    )
    (net (code "80") (name "Net-(PWML-Pad5)") (class "Default")
      (node (ref "PWML") (pin "5") (pinfunction "5_5") (pintype "passive"))
      (node (ref "X2") (pin "17") (pinfunction "17_17") (pintype "passive"))
    )
    (net (code "81") (name "Net-(PWML-Pad6)") (class "Default")
      (node (ref "PWML") (pin "6") (pinfunction "6_6") (pintype "passive"))
      (node (ref "X3") (pin "15") (pinfunction "15_15") (pintype "passive"))
    )
    (net (code "82") (name "Net-(PWML-Pad7)") (class "Default")
      (node (ref "PWML") (pin "7") (pinfunction "7_7") (pintype "passive"))
      (node (ref "X4") (pin "9") (pinfunction "9_9") (pintype "passive"))
    )
    (net (code "83") (name "Net-(Q1-B)") (class "Default")
      (node (ref "Q1") (pin "3") (pinfunction "B_3") (pintype "passive"))
      (node (ref "R3") (pin "1") (pinfunction "1_1") (pintype "passive"))
    )
    (net (code "84") (name "Net-(Q1-C)") (class "Default")
      (node (ref "Q1") (pin "2") (pinfunction "C_2") (pintype "passive"))
      (node (ref "X3") (pin "6") (pinfunction "6_6") (pintype "passive"))
    )
    (net (code "85") (name "Net-(Q2-B)") (class "Default")
      (node (ref "Q2") (pin "3") (pinfunction "B_3") (pintype "passive"))
      (node (ref "R7") (pin "2") (pinfunction "2_2") (pintype "passive"))
    )
    (net (code "86") (name "Net-(Q2-C)") (class "Default")
      (node (ref "JP9") (pin "1") (pinfunction "1_1") (pintype "passive"))
      (node (ref "Q2") (pin "2") (pinfunction "C_2") (pintype "passive"))
    )
    (net (code "87") (name "Net-(U$1-1)") (class "Default")
      (node (ref "R2") (pin "2") (pinfunction "2_2") (pintype "passive"))
      (node (ref "U$1") (pin "PIN1") (pinfunction "1_PIN1") (pintype "bidirectional"))
      (node (ref "U$1") (pin "PIN4") (pinfunction "4_PIN4") (pintype "bidirectional"))
    )
    (net (code "88") (name "Net-(U$2-2)") (class "Default")
      (node (ref "JP5") (pin "7") (pinfunction "7_7") (pintype "passive"))
      (node (ref "U$2") (pin "PIN2") (pinfunction "2_PIN2") (pintype "bidirectional"))
      (node (ref "U$2") (pin "PIN5") (pinfunction "5_PIN5") (pintype "bidirectional"))
    )
    (net (code "89") (name "Net-(X1-Pad14)") (class "Default")
      (node (ref "X1") (pin "14") (pinfunction "14_14") (pintype "passive"))
      (node (ref "X3") (pin "1") (pinfunction "1_1") (pintype "passive"))
    )
    (net (code "90") (name "Net-(X1-Pad23)") (class "Default")
      (node (ref "X1") (pin "23") (pinfunction "23_23") (pintype "passive"))
      (node (ref "XIOL") (pin "16") (pinfunction "16_16") (pintype "passive"))
    )
    (net (code "91") (name "Net-(X2-Pad24)") (class "Default")
      (node (ref "X2") (pin "24") (pinfunction "24_24") (pintype "passive"))
      (node (ref "X5") (pin "8") (pinfunction "8_8") (pintype "passive"))
    )
    (net (code "92") (name "Net-(X3-Pad5)") (class "Default")
      (node (ref "X3") (pin "5") (pinfunction "5_5") (pintype "passive"))
      (node (ref "XIOL") (pin "11") (pinfunction "11_11") (pintype "passive"))
    )
    (net (code "93") (name "Net-(X3-Pad10)") (class "Default")
      (node (ref "X3") (pin "10") (pinfunction "10_10") (pintype "passive"))
      (node (ref "XIOL") (pin "6") (pinfunction "6_6") (pintype "passive"))
    )
    (net (code "94") (name "Net-(X4-Pad4)") (class "Default")
      (node (ref "X4") (pin "4") (pinfunction "4_4") (pintype "passive"))
      (node (ref "XIOL") (pin "9") (pinfunction "9_9") (pintype "passive"))
    )
    (net (code "95") (name "unconnected-(JP5-Pad2)") (class "Default")
      (node (ref "JP5") (pin "2") (pinfunction "2_2") (pintype "passive"))
    )
    (net (code "96") (name "unconnected-(JP5-Pad4)") (class "Default")
      (node (ref "JP5") (pin "4") (pinfunction "4_4") (pintype "passive"))
    )
    (net (code "97") (name "unconnected-(JP5-Pad9)") (class "Default")
      (node (ref "JP5") (pin "9") (pinfunction "9_9") (pintype "passive"))
    )
    (net (code "98") (name "unconnected-(POWER-Pad2)") (class "Default")
      (node (ref "POWER") (pin "2") (pinfunction "2_2") (pintype "passive"))
    )
    (net (code "99") (name "unconnected-(POWER-Pad6)") (class "Default")
      (node (ref "POWER") (pin "6") (pinfunction "6_6") (pintype "passive"))
    )
    (net (code "100") (name "unconnected-(PWMH-Pad3)") (class "Default")
      (node (ref "PWMH") (pin "3") (pinfunction "3_3") (pintype "passive"))
    )
    (net (code "101") (name "unconnected-(PWMH-Pad4)") (class "Default")
      (node (ref "PWMH") (pin "4") (pinfunction "4_4") (pintype "passive"))
    )
    (net (code "102") (name "unconnected-(PWMH-Pad5)") (class "Default")
      (node (ref "PWMH") (pin "5") (pinfunction "5_5") (pintype "passive"))
    )
    (net (code "103") (name "unconnected-(PWMH-Pad6)") (class "Default")
      (node (ref "PWMH") (pin "6") (pinfunction "6_6") (pintype "passive"))
    )
    (net (code "104") (name "unconnected-(PWMH-Pad8)") (class "Default")
      (node (ref "PWMH") (pin "8") (pinfunction "8_8") (pintype "passive"))
    )
    (net (code "105") (name "unconnected-(PWML-Pad2)") (class "Default")
      (node (ref "PWML") (pin "2") (pinfunction "2_2") (pintype "passive"))
    )
  )
)
